# BLE_Test_Board.net
KiCad netlist of a schematic drawn in EAGLE
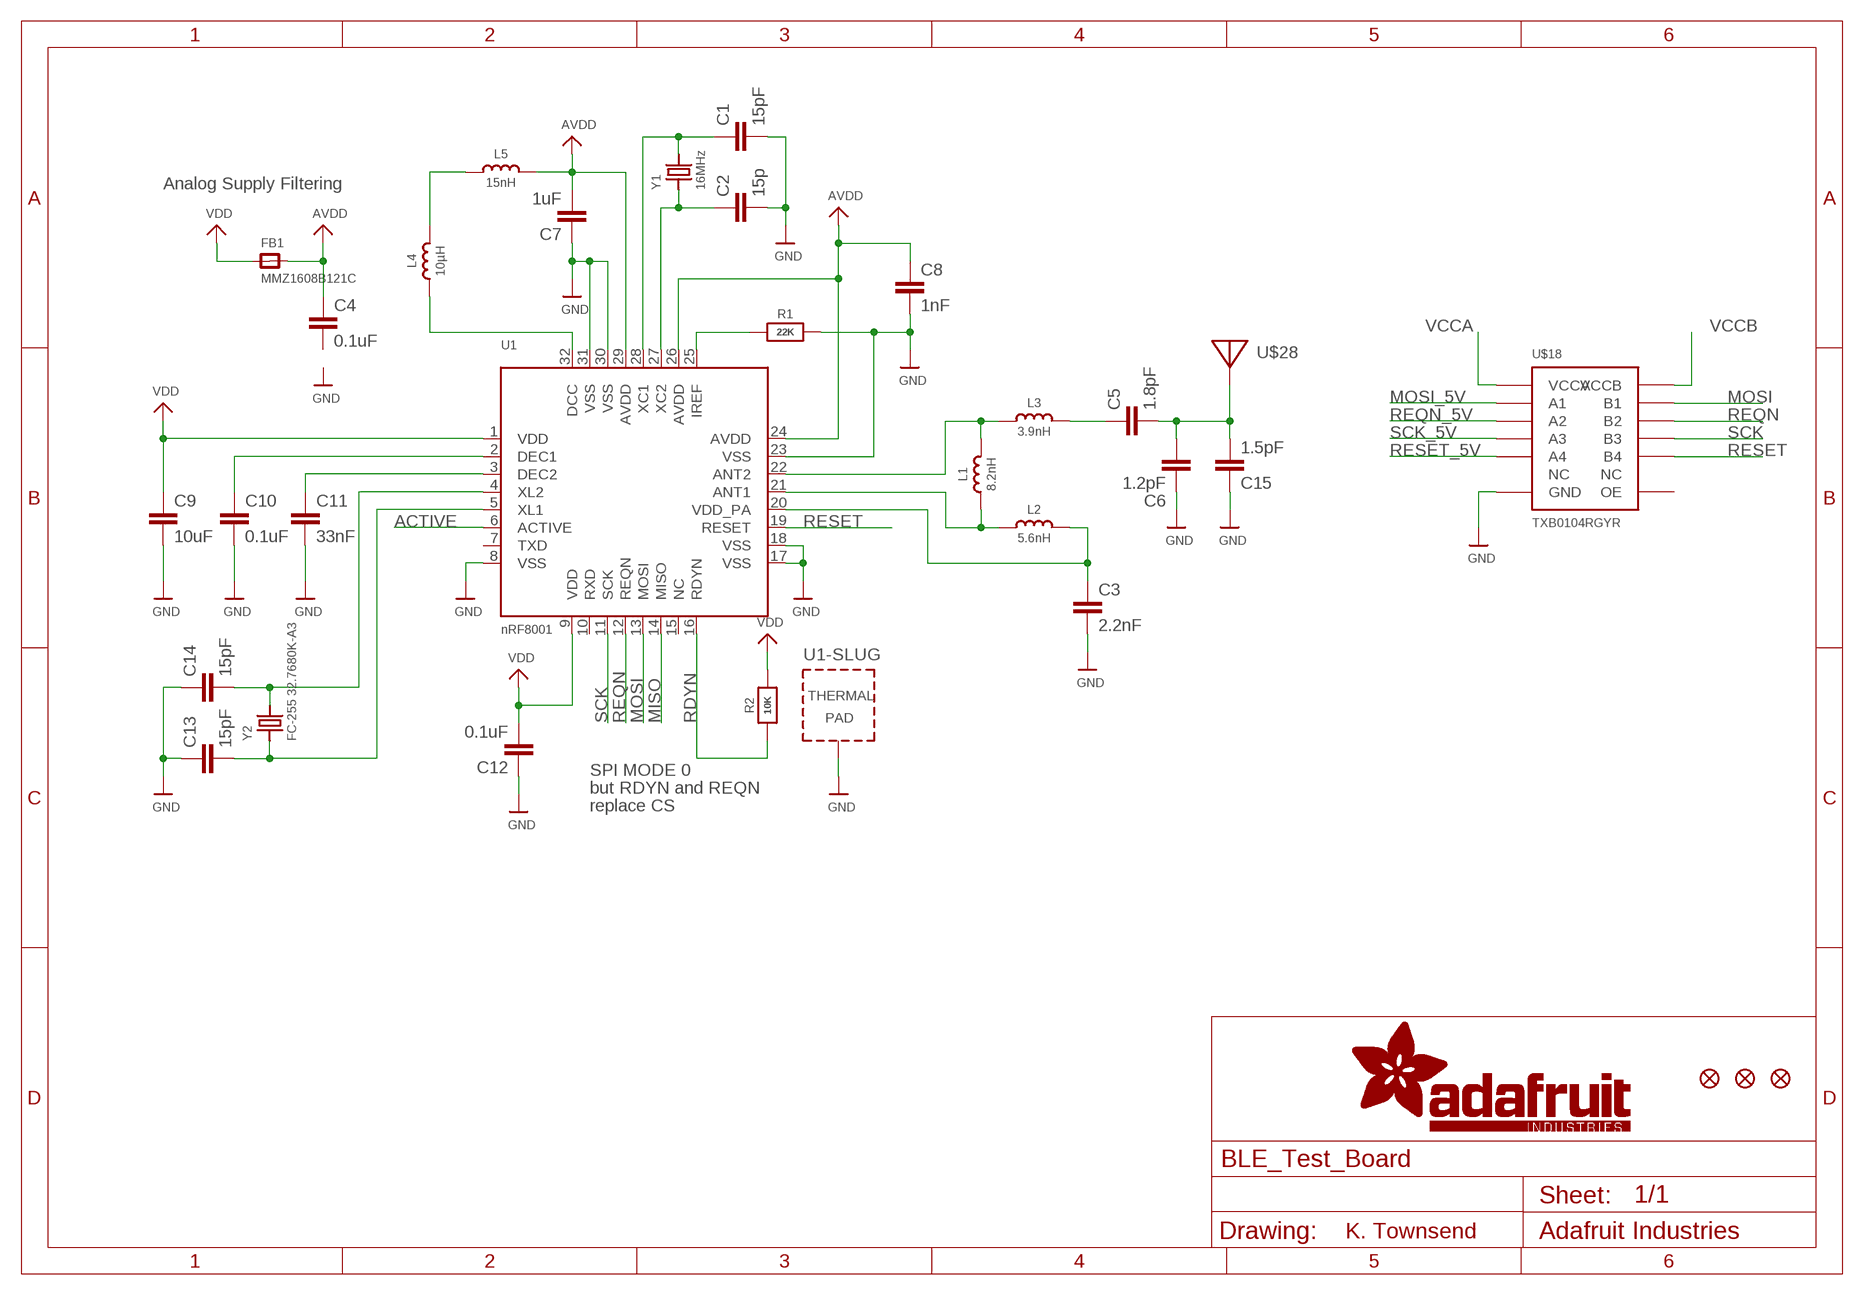
[diagram p0: schematic, sheet 1]

(export (version "E")
  (design (tool "Eeschema 10.0.6"))
  (components
    (comp (ref "C1")
      (value "15pF")
      (footprint "eagle-import:0402-CAP")
      (libsource (lib "eagle-import") (part "CAP0402-CAP"))
    )
    (comp (ref "C2")
      (value "15p")
      (footprint "eagle-import:0402-CAP")
      (libsource (lib "eagle-import") (part "CAP0402-CAP"))
    )
    (comp (ref "C3")
      (value "2.2nF")
      (footprint "eagle-import:0402-CAP")
      (libsource (lib "eagle-import") (part "CAP0402-CAP"))
    )
    (comp (ref "C4")
      (value "0.1uF")
      (footprint "eagle-import:0402-CAP")
      (libsource (lib "eagle-import") (part "CAP0402-CAP"))
    )
    (comp (ref "C5")
      (value "1.8pF")
      (footprint "eagle-import:0402-CAP")
      (libsource (lib "eagle-import") (part "CAP0402-CAP"))
    )
    (comp (ref "C6")
      (value "1.2pF")
      (footprint "eagle-import:0402-CAP")
      (libsource (lib "eagle-import") (part "CAP0402-CAP"))
    )
    (comp (ref "C7")
      (value "1uF")
      (footprint "eagle-import:0402-CAP")
      (libsource (lib "eagle-import") (part "CAP0402-CAP"))
    )
    (comp (ref "C8")
      (value "1nF")
      (footprint "eagle-import:0402-CAP")
      (libsource (lib "eagle-import") (part "CAP0402-CAP"))
    )
    (comp (ref "C9")
      (value "10uF")
      (footprint "eagle-import:0402-CAP")
      (libsource (lib "eagle-import") (part "CAP0402-CAP"))
    )
    (comp (ref "C10")
      (value "0.1uF")
      (footprint "eagle-import:0402-CAP")
      (libsource (lib "eagle-import") (part "CAP0402-CAP"))
    )
    (comp (ref "C11")
      (value "33nF")
      (footprint "eagle-import:0402-CAP")
      (libsource (lib "eagle-import") (part "CAP0402-CAP"))
    )
    (comp (ref "C12")
      (value "0.1uF")
      (footprint "eagle-import:0402-CAP")
      (libsource (lib "eagle-import") (part "CAP0402-CAP"))
    )
    (comp (ref "C13")
      (value "15pF")
      (footprint "eagle-import:0402-CAP")
      (libsource (lib "eagle-import") (part "CAP0402-CAP"))
    )
    (comp (ref "C14")
      (value "15pF")
      (footprint "eagle-import:0402-CAP")
      (libsource (lib "eagle-import") (part "CAP0402-CAP"))
    )
    (comp (ref "C15")
      (value "1.5pF")
      (footprint "eagle-import:0402-CAP")
      (libsource (lib "eagle-import") (part "CAP0402-CAP"))
    )
    (comp (ref "FB1")
      (value "MMZ1608B121C")
      (footprint "eagle-import:0805")
      (libsource (lib "eagle-import") (part "FERRITE0805"))
    )
    (comp (ref "FID1")
      (value "FIDUCIAL\"\"")
      (footprint "eagle-import:FIDUCIAL_1MM")
      (libsource (lib "eagle-import") (part "FIDUCIAL{dblquote}{dblquote}"))
    )
    (comp (ref "FID2")
      (value "FIDUCIAL\"\"")
      (footprint "eagle-import:FIDUCIAL_1MM")
      (libsource (lib "eagle-import") (part "FIDUCIAL{dblquote}{dblquote}"))
    )
    (comp (ref "FID3")
      (value "FIDUCIAL\"\"")
      (footprint "eagle-import:FIDUCIAL_1MM")
      (fields (field (name "BOM") "EXCLUDE"))
      (libsource (lib "eagle-import") (part "FIDUCIAL{dblquote}{dblquote}"))
    )
    (comp (ref "L1")
      (value "8.2nH")
      (footprint "eagle-import:_0402")
      (libsource (lib "eagle-import") (part "INDUCTOR_0402"))
    )
    (comp (ref "L2")
      (value "5.6nH")
      (footprint "eagle-import:_0402")
      (libsource (lib "eagle-import") (part "INDUCTOR_0402"))
    )
    (comp (ref "L3")
      (value "3.9nH")
      (footprint "eagle-import:_0402")
      (libsource (lib "eagle-import") (part "INDUCTOR_0402"))
    )
    (comp (ref "L4")
      (value "10µH")
      (footprint "eagle-import:_0603")
      (libsource (lib "eagle-import") (part "INDUCTOR_0603"))
    )
    (comp (ref "L5")
      (value "15nH")
      (footprint "eagle-import:_0603")
      (libsource (lib "eagle-import") (part "INDUCTOR_0603"))
    )
    (comp (ref "R1")
      (value "22K")
      (footprint "eagle-import:_0805MP")
      (libsource (lib "eagle-import") (part "RESISTOR_0805MP"))
    )
    (comp (ref "R2")
      (value "10K")
      (footprint "eagle-import:0805-NO")
      (libsource (lib "eagle-import") (part "RESISTOR0805_NOOUTLINE"))
    )
    (comp (ref "U$18")
      (value "TXB0104RGYR")
      (footprint "eagle-import:14-VFQFN-EXPOSED-PAD")
      (libsource (lib "eagle-import") (part "TXB0104RGYR"))
    )
    (comp (ref "U$28")
      (value "ANTENNA_PCBNRF8001_1.6MM")
      (footprint "eagle-import:ANT_PCB_2.4GHZ_NRF8001_1.6MM_1OZ")
      (libsource (lib "eagle-import") (part "ANTENNA_PCBNRF8001_1.6MM"))
    )
    (comp (ref "U1")
      (value "nRF8001")
      (footprint "eagle-import:QFN32_5MM")
      (libsource (lib "eagle-import") (part "NRF8001"))
    )
    (comp (ref "Y1")
      (value "16MHz")
      (footprint "eagle-import:CRYSTAL_2.5X2")
      (libsource (lib "eagle-import") (part "CRYSTAL2.5X2.0"))
    )
    (comp (ref "Y2")
      (value "FC-255 32.7680K-A3")
      (footprint "eagle-import:CRYSTAL_4.9X1.8")
      (libsource (lib "eagle-import") (part "CRYSTAL4.9X1.8"))
    )
  )
  (nets
    (net (code "1") (name "/ACTIVE") (class "Default")
      (node (ref "U1") (pin "6") (pinfunction "ACTIVE_6") (pintype "output"))
    )
    (net (code "2") (name "/MISO") (class "Default")
      (node (ref "U1") (pin "14") (pinfunction "MISO_14") (pintype "output"))
    )
    (net (code "3") (name "/MOSI") (class "Default")
      (node (ref "U$18") (pin "P$13") (pinfunction "B1_P$13") (pintype "bidirectional"))
      (node (ref "U1") (pin "13") (pinfunction "MOSI_13") (pintype "input"))
    )
    (net (code "4") (name "/MOSI_5V") (class "Default")
      (node (ref "U$18") (pin "P$2") (pinfunction "A1_P$2") (pintype "bidirectional"))
    )
    (net (code "5") (name "/RDYN") (class "Default")
      (node (ref "R2") (pin "1") (pinfunction "1_1") (pintype "passive"))
      (node (ref "U1") (pin "16") (pinfunction "RDYN_16") (pintype "output"))
    )
    (net (code "6") (name "/REQN") (class "Default")
      (node (ref "U$18") (pin "P$12") (pinfunction "B2_P$12") (pintype "bidirectional"))
      (node (ref "U1") (pin "12") (pinfunction "REQN_12") (pintype "input"))
    )
    (net (code "7") (name "/REQN_5V") (class "Default")
      (node (ref "U$18") (pin "P$3") (pinfunction "A2_P$3") (pintype "bidirectional"))
    )
    (net (code "8") (name "/RESET") (class "Default")
      (node (ref "U$18") (pin "P$10") (pinfunction "B4_P$10") (pintype "bidirectional"))
      (node (ref "U1") (pin "19") (pinfunction "RESET_19") (pintype "input"))
    )
    (net (code "9") (name "/RESET_5V") (class "Default")
      (node (ref "U$18") (pin "P$5") (pinfunction "A4_P$5") (pintype "bidirectional"))
    )
    (net (code "10") (name "/SCK") (class "Default")
      (node (ref "U$18") (pin "P$11") (pinfunction "B3_P$11") (pintype "bidirectional"))
      (node (ref "U1") (pin "11") (pinfunction "SCK_11") (pintype "input"))
    )
    (net (code "11") (name "/SCK_5V") (class "Default")
      (node (ref "U$18") (pin "P$4") (pinfunction "A3_P$4") (pintype "bidirectional"))
    )
    (net (code "12") (name "/VCCA") (class "Default")
      (node (ref "U$18") (pin "P$1") (pinfunction "VCCA_P$1") (pintype "bidirectional"))
    )
    (net (code "13") (name "/VCCB") (class "Default")
      (node (ref "U$18") (pin "P$14") (pinfunction "VCCB_P$14") (pintype "bidirectional"))
    )
    (net (code "14") (name "AVDD") (class "Default")
      (node (ref "C4") (pin "1") (pinfunction "1_1") (pintype "passive"))
      (node (ref "C7") (pin "2") (pinfunction "2_2") (pintype "passive"))
      (node (ref "C8") (pin "1") (pinfunction "1_1") (pintype "passive"))
      (node (ref "FB1") (pin "2") (pinfunction "P$2_2") (pintype "passive"))
      (node (ref "L5") (pin "2") (pinfunction "2_2") (pintype "passive"))
      (node (ref "U1") (pin "24") (pinfunction "AVDD_24") (pintype "power_in"))
      (node (ref "U1") (pin "26") (pinfunction "AVDD_26") (pintype "power_in"))
      (node (ref "U1") (pin "29") (pinfunction "AVDD_29") (pintype "power_in"))
    )
    (net (code "15") (name "GND") (class "Default")
      (node (ref "C1") (pin "2") (pinfunction "2_2") (pintype "passive"))
      (node (ref "C10") (pin "2") (pinfunction "2_2") (pintype "passive"))
      (node (ref "C11") (pin "2") (pinfunction "2_2") (pintype "passive"))
      (node (ref "C12") (pin "1") (pinfunction "1_1") (pintype "passive"))
      (node (ref "C13") (pin "1") (pinfunction "1_1") (pintype "passive"))
      (node (ref "C14") (pin "1") (pinfunction "1_1") (pintype "passive"))
      (node (ref "C15") (pin "1") (pinfunction "1_1") (pintype "passive"))
      (node (ref "C2") (pin "2") (pinfunction "2_2") (pintype "passive"))
      (node (ref "C3") (pin "2") (pinfunction "2_2") (pintype "passive"))
      (node (ref "C6") (pin "1") (pinfunction "1_1") (pintype "passive"))
      (node (ref "C7") (pin "1") (pinfunction "1_1") (pintype "passive"))
      (node (ref "C8") (pin "2") (pinfunction "2_2") (pintype "passive"))
      (node (ref "C9") (pin "2") (pinfunction "2_2") (pintype "passive"))
      (node (ref "R1") (pin "2") (pinfunction "2_2") (pintype "passive"))
      (node (ref "U$18") (pin "P$7") (pinfunction "GND_P$7") (pintype "bidirectional"))
      (node (ref "U1") (pin "17") (pinfunction "VSS_17") (pintype "power_in"))
      (node (ref "U1") (pin "18") (pinfunction "VSS_18") (pintype "power_in"))
      (node (ref "U1") (pin "23") (pinfunction "VSS_23") (pintype "power_in"))
      (node (ref "U1") (pin "30") (pinfunction "VSS_30") (pintype "power_in"))
      (node (ref "U1") (pin "31") (pinfunction "VSS_31") (pintype "power_in"))
      (node (ref "U1") (pin "33") (pinfunction "TP_33") (pintype "power_in"))
      (node (ref "U1") (pin "8") (pinfunction "VSS_8") (pintype "power_in"))
    )
    (net (code "16") (name "Net-(C5-Pad1)") (class "Default")
      (node (ref "C5") (pin "1") (pinfunction "1_1") (pintype "passive"))
      (node (ref "L3") (pin "2") (pinfunction "2_2") (pintype "passive"))
    )
    (net (code "17") (name "Net-(L4-Pad2)") (class "Default")
      (node (ref "L4") (pin "2") (pinfunction "2_2") (pintype "passive"))
      (node (ref "L5") (pin "1") (pinfunction "1_1") (pintype "passive"))
    )
    (net (code "18") (name "Net-(U$28-P$1)") (class "Default")
      (node (ref "C15") (pin "2") (pinfunction "2_2") (pintype "passive"))
      (node (ref "C5") (pin "2") (pinfunction "2_2") (pintype "passive"))
      (node (ref "C6") (pin "2") (pinfunction "2_2") (pintype "passive"))
      (node (ref "U$28") (pin "FEED") (pinfunction "P$1_FEED") (pintype "passive"))
    )
    (net (code "19") (name "Net-(U1B-ANT1)") (class "Default")
      (node (ref "L1") (pin "1") (pinfunction "1_1") (pintype "passive"))
      (node (ref "L2") (pin "1") (pinfunction "1_1") (pintype "passive"))
      (node (ref "U1") (pin "21") (pinfunction "ANT1_21") (pintype "bidirectional"))
    )
    (net (code "20") (name "Net-(U1B-ANT2)") (class "Default")
      (node (ref "L1") (pin "2") (pinfunction "2_2") (pintype "passive"))
      (node (ref "L3") (pin "1") (pinfunction "1_1") (pintype "passive"))
      (node (ref "U1") (pin "22") (pinfunction "ANT2_22") (pintype "bidirectional"))
    )
    (net (code "21") (name "Net-(U1B-DCC)") (class "Default")
      (node (ref "L4") (pin "1") (pinfunction "1_1") (pintype "passive"))
      (node (ref "U1") (pin "32") (pinfunction "DCC_32") (pintype "bidirectional"))
    )
    (net (code "22") (name "Net-(U1B-DEC1)") (class "Default")
      (node (ref "C10") (pin "1") (pinfunction "1_1") (pintype "passive"))
      (node (ref "U1") (pin "2") (pinfunction "DEC1_2") (pintype "bidirectional"))
    )
    (net (code "23") (name "Net-(U1B-DEC2)") (class "Default")
      (node (ref "C11") (pin "1") (pinfunction "1_1") (pintype "passive"))
      (node (ref "U1") (pin "3") (pinfunction "DEC2_3") (pintype "bidirectional"))
    )
    (net (code "24") (name "Net-(U1B-IREF)") (class "Default")
      (node (ref "R1") (pin "1") (pinfunction "1_1") (pintype "passive"))
      (node (ref "U1") (pin "25") (pinfunction "IREF_25") (pintype "output"))
    )
    (net (code "25") (name "Net-(U1B-VDD_PA)") (class "Default")
      (node (ref "C3") (pin "1") (pinfunction "1_1") (pintype "passive"))
      (node (ref "L2") (pin "2") (pinfunction "2_2") (pintype "passive"))
      (node (ref "U1") (pin "20") (pinfunction "VDD_PA_20") (pintype "bidirectional"))
    )
    (net (code "26") (name "Net-(U1B-XC1)") (class "Default")
      (node (ref "C1") (pin "1") (pinfunction "1_1") (pintype "passive"))
      (node (ref "U1") (pin "28") (pinfunction "XC1_28") (pintype "input"))
      (node (ref "Y1") (pin "3") (pinfunction "2_3") (pintype "passive"))
    )
    (net (code "27") (name "Net-(U1B-XC2)") (class "Default")
      (node (ref "C2") (pin "1") (pinfunction "1_1") (pintype "passive"))
      (node (ref "U1") (pin "27") (pinfunction "XC2_27") (pintype "output"))
      (node (ref "Y1") (pin "1") (pinfunction "1_1") (pintype "passive"))
    )
    (net (code "28") (name "Net-(U1B-XL1)") (class "Default")
      (node (ref "C13") (pin "2") (pinfunction "2_2") (pintype "passive"))
      (node (ref "U1") (pin "5") (pinfunction "XL1_5") (pintype "input"))
      (node (ref "Y2") (pin "1") (pinfunction "1_1") (pintype "passive"))
    )
    (net (code "29") (name "Net-(U1B-XL2)") (class "Default")
      (node (ref "C14") (pin "2") (pinfunction "2_2") (pintype "passive"))
      (node (ref "U1") (pin "4") (pinfunction "XL2_4") (pintype "output"))
      (node (ref "Y2") (pin "2") (pinfunction "2_2") (pintype "passive"))
    )
    (net (code "30") (name "VDD") (class "Default")
      (node (ref "C12") (pin "2") (pinfunction "2_2") (pintype "passive"))
      (node (ref "C9") (pin "1") (pinfunction "1_1") (pintype "passive"))
      (node (ref "FB1") (pin "1") (pinfunction "P$1_1") (pintype "passive"))
      (node (ref "R2") (pin "2") (pinfunction "2_2") (pintype "passive"))
      (node (ref "U1") (pin "1") (pinfunction "VDD_1") (pintype "power_in"))
      (node (ref "U1") (pin "9") (pinfunction "VDD_9") (pintype "power_in"))
    )
    (net (code "31") (name "unconnected-(C4-Pad2)") (class "Default")
      (node (ref "C4") (pin "2") (pinfunction "2_2") (pintype "passive"))
    )
    (net (code "32") (name "unconnected-(U$18-NC-PadP$6)") (class "Default")
      (node (ref "U$18") (pin "P$6") (pinfunction "NC_P$6") (pintype "bidirectional"))
    )
    (net (code "33") (name "unconnected-(U$18-NC-PadP$9)") (class "Default")
      (node (ref "U$18") (pin "P$9") (pinfunction "NC_P$9") (pintype "bidirectional"))
    )
    (net (code "34") (name "unconnected-(U$18-OE-PadP$8)") (class "Default")
      (node (ref "U$18") (pin "P$8") (pinfunction "OE_P$8") (pintype "bidirectional"))
    )
    (net (code "35") (name "unconnected-(U1B-NC-Pad15)") (class "Default")
      (node (ref "U1") (pin "15") (pinfunction "NC_15") (pintype "no_connect"))
    )
    (net (code "36") (name "unconnected-(U1B-RXD-Pad10)") (class "Default")
      (node (ref "U1") (pin "10") (pinfunction "RXD_10") (pintype "input"))
    )
    (net (code "37") (name "unconnected-(U1B-TXD-Pad7)") (class "Default")
      (node (ref "U1") (pin "7") (pinfunction "TXD_7") (pintype "output"))
    )
  )
)
